# PowerNode_v1.net
KiCad netlist of a schematic drawn in EAGLE
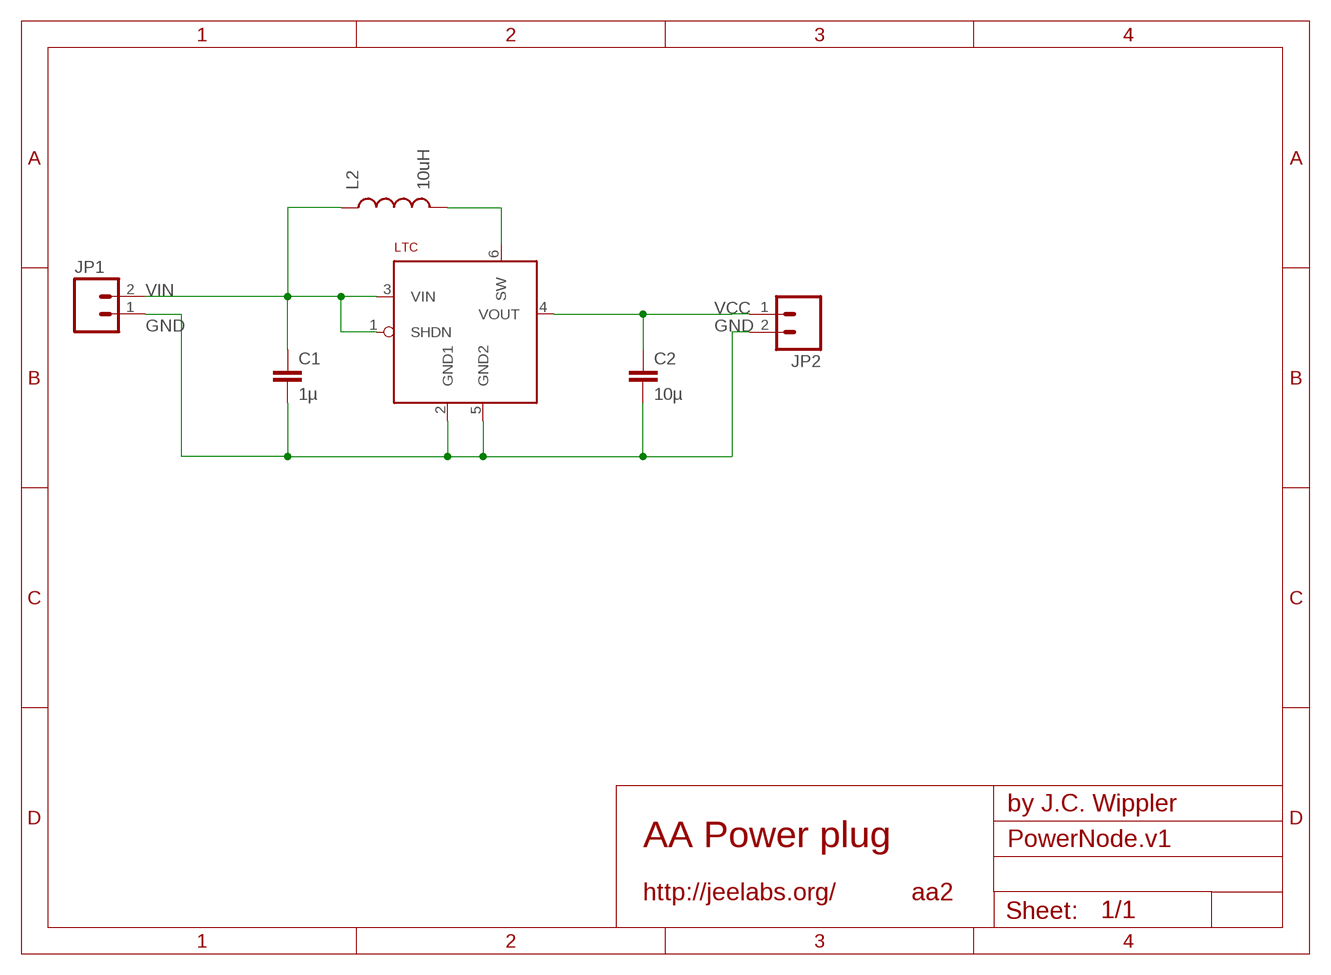
[diagram p0: schematic, sheet 1]

(export (version "E")
  (design (tool "Eeschema 10.0.6"))
  (components
    (comp (ref "C1")
      (value "1µ")
      (footprint "eagle-import:0603-CAP")
      (libsource (lib "eagle-import") (part "CAP0603-CAP"))
    )
    (comp (ref "C2")
      (value "10µ")
      (footprint "eagle-import:0805")
      (libsource (lib "eagle-import") (part "CAP0805"))
    )
    (comp (ref "JP1")
      (value "M02PTH")
      (footprint "eagle-import:1X02")
      (libsource (lib "eagle-import") (part "M02PTH"))
    )
    (comp (ref "JP2")
      (value "M02PTH")
      (footprint "eagle-import:1X02")
      (libsource (lib "eagle-import") (part "M02PTH"))
    )
    (comp (ref "L2")
      (value "10uH")
      (footprint "eagle-import:CR54")
      (libsource (lib "eagle-import") (part "INDUCTORCR54"))
    )
    (comp (ref "LTC")
      (value "LTC3525")
      (footprint "eagle-import:SC70")
      (libsource (lib "eagle-import") (part "LTC3525"))
    )
  )
  (nets
    (net (code "1") (name "/GND") (class "Default")
      (node (ref "C1") (pin "2") (pinfunction "2_2") (pintype "passive"))
      (node (ref "C2") (pin "2") (pinfunction "2_2") (pintype "passive"))
      (node (ref "JP1") (pin "1") (pinfunction "1_1") (pintype "passive"))
      (node (ref "JP2") (pin "2") (pinfunction "2_2") (pintype "passive"))
      (node (ref "LTC") (pin "2") (pinfunction "GND1_2") (pintype "power_in"))
      (node (ref "LTC") (pin "5") (pinfunction "GND2_5") (pintype "power_in"))
    )
    (net (code "2") (name "/VCC") (class "Default")
      (node (ref "C2") (pin "1") (pinfunction "1_1") (pintype "passive"))
      (node (ref "JP2") (pin "1") (pinfunction "1_1") (pintype "passive"))
      (node (ref "LTC") (pin "4") (pinfunction "VOUT_4") (pintype "power_in"))
    )
    (net (code "3") (name "/VIN") (class "Default")
      (node (ref "C1") (pin "1") (pinfunction "1_1") (pintype "passive"))
      (node (ref "JP1") (pin "2") (pinfunction "2_2") (pintype "passive"))
      (node (ref "L2") (pin "P$1") (pinfunction "1_P$1") (pintype "passive"))
      (node (ref "LTC") (pin "1") (pinfunction "SHDN_1") (pintype "input"))
      (node (ref "LTC") (pin "3") (pinfunction "VIN_3") (pintype "tri_state"))
    )
    (net (code "4") (name "Net-(L2-2)") (class "Default")
      (node (ref "L2") (pin "P$2") (pinfunction "2_P$2") (pintype "passive"))
      (node (ref "LTC") (pin "6") (pinfunction "SW_6") (pintype "power_in"))
    )
  )
)
